# foArduinoMega.net
KiCad netlist of a schematic drawn in EAGLE
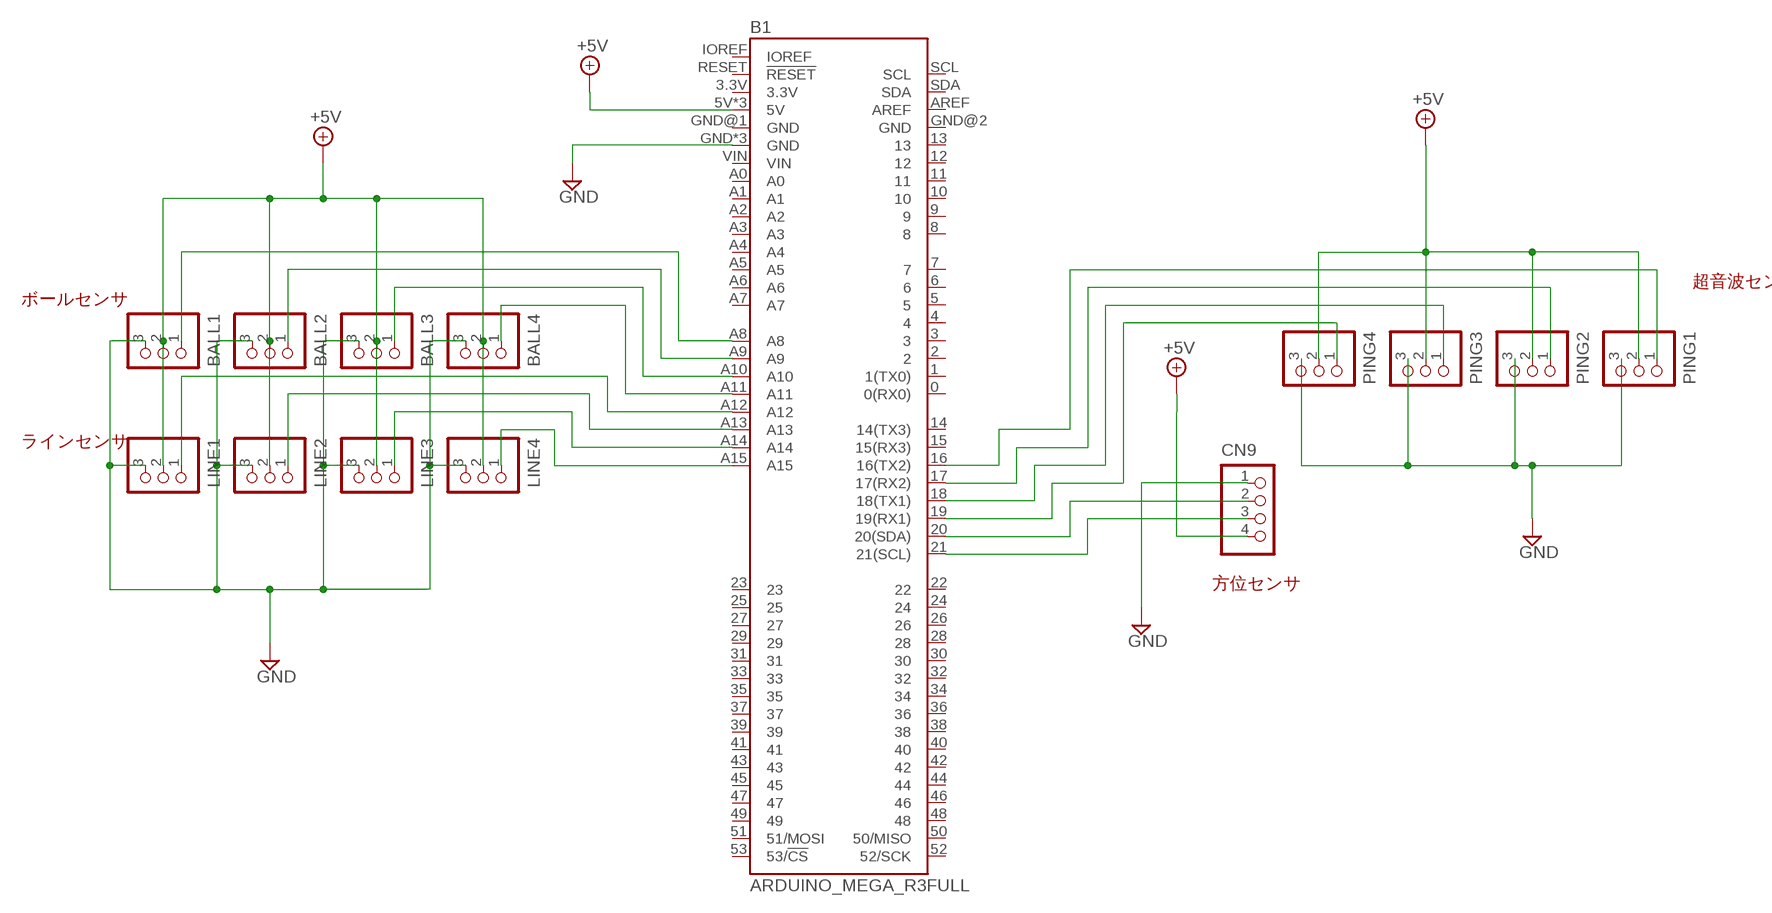
[diagram p0: schematic, sheet 1]

(export (version "E")
  (design (tool "Eeschema 10.0.6"))
  (components
    (comp (ref "B1")
      (value "ARDUINO_MEGA_R3FULL")
      (footprint "eagle-import:ARDUINO_MEGA_NO_SILK")
      (libsource (lib "eagle-import") (part "ARDUINO_MEGA_R3FULL"))
    )
    (comp (ref "BALL1")
      (value "B3B-XH-A")
      (footprint "eagle-import:B3B-XH-A")
      (libsource (lib "eagle-import") (part "B3B-XH-A"))
    )
    (comp (ref "BALL2")
      (value "B3B-XH-A")
      (footprint "eagle-import:B3B-XH-A")
      (libsource (lib "eagle-import") (part "B3B-XH-A"))
    )
    (comp (ref "BALL3")
      (value "B3B-XH-A")
      (footprint "eagle-import:B3B-XH-A")
      (libsource (lib "eagle-import") (part "B3B-XH-A"))
    )
    (comp (ref "BALL4")
      (value "B3B-XH-A")
      (footprint "eagle-import:B3B-XH-A")
      (libsource (lib "eagle-import") (part "B3B-XH-A"))
    )
    (comp (ref "CN9")
      (value "B4B-XH-A")
      (footprint "eagle-import:B4B-XH-A")
      (libsource (lib "eagle-import") (part "B4B-XH-A"))
    )
    (comp (ref "LINE1")
      (value "B3B-XH-A")
      (footprint "eagle-import:B3B-XH-A")
      (libsource (lib "eagle-import") (part "B3B-XH-A"))
    )
    (comp (ref "LINE2")
      (value "B3B-XH-A")
      (footprint "eagle-import:B3B-XH-A")
      (libsource (lib "eagle-import") (part "B3B-XH-A"))
    )
    (comp (ref "LINE3")
      (value "B3B-XH-A")
      (footprint "eagle-import:B3B-XH-A")
      (libsource (lib "eagle-import") (part "B3B-XH-A"))
    )
    (comp (ref "LINE4")
      (value "B3B-XH-A")
      (footprint "eagle-import:B3B-XH-A")
      (libsource (lib "eagle-import") (part "B3B-XH-A"))
    )
    (comp (ref "PING1")
      (value "B3B-XH-A")
      (footprint "eagle-import:B3B-XH-A")
      (libsource (lib "eagle-import") (part "B3B-XH-A"))
    )
    (comp (ref "PING2")
      (value "B3B-XH-A")
      (footprint "eagle-import:B3B-XH-A")
      (libsource (lib "eagle-import") (part "B3B-XH-A"))
    )
    (comp (ref "PING3")
      (value "B3B-XH-A")
      (footprint "eagle-import:B3B-XH-A")
      (libsource (lib "eagle-import") (part "B3B-XH-A"))
    )
    (comp (ref "PING4")
      (value "B3B-XH-A")
      (footprint "eagle-import:B3B-XH-A")
      (libsource (lib "eagle-import") (part "B3B-XH-A"))
    )
  )
  (nets
    (net (code "1") (name "+5V") (class "Default")
      (node (ref "B1") (pin "5V") (pinfunction "5V_5V") (pintype "bidirectional"))
      (node (ref "B1") (pin "5V@1") (pinfunction "5V_5V@1") (pintype "bidirectional"))
      (node (ref "B1") (pin "5V@2") (pinfunction "5V_5V@2") (pintype "bidirectional"))
      (node (ref "BALL1") (pin "2") (pinfunction "2_2") (pintype "passive"))
      (node (ref "BALL2") (pin "2") (pinfunction "2_2") (pintype "passive"))
      (node (ref "BALL3") (pin "2") (pinfunction "2_2") (pintype "passive"))
      (node (ref "BALL4") (pin "2") (pinfunction "2_2") (pintype "passive"))
      (node (ref "CN9") (pin "4") (pinfunction "4_4") (pintype "passive"))
      (node (ref "LINE1") (pin "2") (pinfunction "2_2") (pintype "passive"))
      (node (ref "LINE2") (pin "2") (pinfunction "2_2") (pintype "passive"))
      (node (ref "LINE3") (pin "2") (pinfunction "2_2") (pintype "passive"))
      (node (ref "LINE4") (pin "2") (pinfunction "2_2") (pintype "passive"))
      (node (ref "PING1") (pin "2") (pinfunction "2_2") (pintype "passive"))
      (node (ref "PING2") (pin "2") (pinfunction "2_2") (pintype "passive"))
      (node (ref "PING3") (pin "2") (pinfunction "2_2") (pintype "passive"))
      (node (ref "PING4") (pin "2") (pinfunction "2_2") (pintype "passive"))
    )
    (net (code "2") (name "GND") (class "Default")
      (node (ref "B1") (pin "GND") (pinfunction "GND_GND") (pintype "bidirectional"))
      (node (ref "B1") (pin "GND@3") (pinfunction "GND_GND@3") (pintype "bidirectional"))
      (node (ref "B1") (pin "GND@4") (pinfunction "GND_GND@4") (pintype "bidirectional"))
      (node (ref "BALL1") (pin "3") (pinfunction "3_3") (pintype "passive"))
      (node (ref "BALL2") (pin "3") (pinfunction "3_3") (pintype "passive"))
      (node (ref "BALL3") (pin "3") (pinfunction "3_3") (pintype "passive"))
      (node (ref "BALL4") (pin "3") (pinfunction "3_3") (pintype "passive"))
      (node (ref "CN9") (pin "1") (pinfunction "1_1") (pintype "passive"))
      (node (ref "LINE1") (pin "3") (pinfunction "3_3") (pintype "passive"))
      (node (ref "LINE2") (pin "3") (pinfunction "3_3") (pintype "passive"))
      (node (ref "LINE3") (pin "3") (pinfunction "3_3") (pintype "passive"))
      (node (ref "LINE4") (pin "3") (pinfunction "3_3") (pintype "passive"))
      (node (ref "PING1") (pin "3") (pinfunction "3_3") (pintype "passive"))
      (node (ref "PING2") (pin "3") (pinfunction "3_3") (pintype "passive"))
      (node (ref "PING3") (pin "3") (pinfunction "3_3") (pintype "passive"))
      (node (ref "PING4") (pin "3") (pinfunction "3_3") (pintype "passive"))
    )
    (net (code "3") (name "Net-(B1-16(TX2))") (class "Default")
      (node (ref "B1") (pin "16") (pinfunction "16(TX2)_16") (pintype "bidirectional"))
      (node (ref "PING1") (pin "1") (pinfunction "1_1") (pintype "passive"))
    )
    (net (code "4") (name "Net-(B1-17(RX2))") (class "Default")
      (node (ref "B1") (pin "17") (pinfunction "17(RX2)_17") (pintype "bidirectional"))
      (node (ref "PING2") (pin "1") (pinfunction "1_1") (pintype "passive"))
    )
    (net (code "5") (name "Net-(B1-18(TX1))") (class "Default")
      (node (ref "B1") (pin "18") (pinfunction "18(TX1)_18") (pintype "bidirectional"))
      (node (ref "PING3") (pin "1") (pinfunction "1_1") (pintype "passive"))
    )
    (net (code "6") (name "Net-(B1-19(RX1))") (class "Default")
      (node (ref "B1") (pin "19") (pinfunction "19(RX1)_19") (pintype "bidirectional"))
      (node (ref "PING4") (pin "1") (pinfunction "1_1") (pintype "passive"))
    )
    (net (code "7") (name "Net-(B1-20(SDA))") (class "Default")
      (node (ref "B1") (pin "20") (pinfunction "20(SDA)_20") (pintype "bidirectional"))
      (node (ref "CN9") (pin "2") (pinfunction "2_2") (pintype "passive"))
    )
    (net (code "8") (name "Net-(B1-21(SCL))") (class "Default")
      (node (ref "B1") (pin "21") (pinfunction "21(SCL)_21") (pintype "bidirectional"))
      (node (ref "CN9") (pin "3") (pinfunction "3_3") (pintype "passive"))
    )
    (net (code "9") (name "Net-(B1-PadA8)") (class "Default")
      (node (ref "B1") (pin "A8") (pinfunction "A8_A8") (pintype "bidirectional"))
      (node (ref "BALL1") (pin "1") (pinfunction "1_1") (pintype "passive"))
    )
    (net (code "10") (name "Net-(B1-PadA9)") (class "Default")
      (node (ref "B1") (pin "A9") (pinfunction "A9_A9") (pintype "bidirectional"))
      (node (ref "BALL2") (pin "1") (pinfunction "1_1") (pintype "passive"))
    )
    (net (code "11") (name "Net-(B1-PadA10)") (class "Default")
      (node (ref "B1") (pin "A10") (pinfunction "A10_A10") (pintype "bidirectional"))
      (node (ref "BALL3") (pin "1") (pinfunction "1_1") (pintype "passive"))
    )
    (net (code "12") (name "Net-(B1-PadA11)") (class "Default")
      (node (ref "B1") (pin "A11") (pinfunction "A11_A11") (pintype "bidirectional"))
      (node (ref "BALL4") (pin "1") (pinfunction "1_1") (pintype "passive"))
    )
    (net (code "13") (name "Net-(B1-PadA12)") (class "Default")
      (node (ref "B1") (pin "A12") (pinfunction "A12_A12") (pintype "bidirectional"))
      (node (ref "LINE1") (pin "1") (pinfunction "1_1") (pintype "passive"))
    )
    (net (code "14") (name "Net-(B1-PadA13)") (class "Default")
      (node (ref "B1") (pin "A13") (pinfunction "A13_A13") (pintype "bidirectional"))
      (node (ref "LINE2") (pin "1") (pinfunction "1_1") (pintype "passive"))
    )
    (net (code "15") (name "Net-(B1-PadA14)") (class "Default")
      (node (ref "B1") (pin "A14") (pinfunction "A14_A14") (pintype "bidirectional"))
      (node (ref "LINE3") (pin "1") (pinfunction "1_1") (pintype "passive"))
    )
    (net (code "16") (name "Net-(B1-PadA15)") (class "Default")
      (node (ref "B1") (pin "A15") (pinfunction "A15_A15") (pintype "bidirectional"))
      (node (ref "LINE4") (pin "1") (pinfunction "1_1") (pintype "passive"))
    )
    (net (code "17") (name "unconnected-(B1-0(RX0)-Pad0)") (class "Default")
      (node (ref "B1") (pin "0") (pinfunction "0(RX0)_0") (pintype "bidirectional"))
    )
    (net (code "18") (name "unconnected-(B1-1(TX0)-Pad1)") (class "Default")
      (node (ref "B1") (pin "1") (pinfunction "1(TX0)_1") (pintype "bidirectional"))
    )
    (net (code "19") (name "unconnected-(B1-14(TX3)-Pad14)") (class "Default")
      (node (ref "B1") (pin "14") (pinfunction "14(TX3)_14") (pintype "bidirectional"))
    )
    (net (code "20") (name "unconnected-(B1-15(RX3)-Pad15)") (class "Default")
      (node (ref "B1") (pin "15") (pinfunction "15(RX3)_15") (pintype "bidirectional"))
    )
    (net (code "21") (name "unconnected-(B1-50{slash}MISO-Pad50)") (class "Default")
      (node (ref "B1") (pin "50") (pinfunction "50/MISO_50") (pintype "bidirectional"))
    )
    (net (code "22") (name "unconnected-(B1-51{slash}MOSI-Pad51)") (class "Default")
      (node (ref "B1") (pin "51") (pinfunction "51/MOSI_51") (pintype "bidirectional"))
    )
    (net (code "23") (name "unconnected-(B1-52{slash}SCK-Pad52)") (class "Default")
      (node (ref "B1") (pin "52") (pinfunction "52/SCK_52") (pintype "bidirectional"))
    )
    (net (code "24") (name "unconnected-(B1-53{slash}~{CS}-Pad53)") (class "Default")
      (node (ref "B1") (pin "53") (pinfunction "53/~{CS}_53") (pintype "bidirectional"))
    )
    (net (code "25") (name "unconnected-(B1-GND-PadGND@1)") (class "Default")
      (node (ref "B1") (pin "GND@1") (pinfunction "GND_GND@1") (pintype "bidirectional"))
    )
    (net (code "26") (name "unconnected-(B1-GND-PadGND@2)") (class "Default")
      (node (ref "B1") (pin "GND@2") (pinfunction "GND_GND@2") (pintype "bidirectional"))
    )
    (net (code "27") (name "unconnected-(B1-Pad2)") (class "Default")
      (node (ref "B1") (pin "2") (pinfunction "2_2") (pintype "bidirectional"))
    )
    (net (code "28") (name "unconnected-(B1-Pad3)") (class "Default")
      (node (ref "B1") (pin "3") (pinfunction "3_3") (pintype "bidirectional"))
    )
    (net (code "29") (name "unconnected-(B1-Pad3.3V)") (class "Default")
      (node (ref "B1") (pin "3.3V") (pinfunction "3.3V_3.3V") (pintype "bidirectional"))
    )
    (net (code "30") (name "unconnected-(B1-Pad4)") (class "Default")
      (node (ref "B1") (pin "4") (pinfunction "4_4") (pintype "bidirectional"))
    )
    (net (code "31") (name "unconnected-(B1-Pad5)") (class "Default")
      (node (ref "B1") (pin "5") (pinfunction "5_5") (pintype "bidirectional"))
    )
    (net (code "32") (name "unconnected-(B1-Pad6)") (class "Default")
      (node (ref "B1") (pin "6") (pinfunction "6_6") (pintype "bidirectional"))
    )
    (net (code "33") (name "unconnected-(B1-Pad7)") (class "Default")
      (node (ref "B1") (pin "7") (pinfunction "7_7") (pintype "bidirectional"))
    )
    (net (code "34") (name "unconnected-(B1-Pad8)") (class "Default")
      (node (ref "B1") (pin "8") (pinfunction "8_8") (pintype "bidirectional"))
    )
    (net (code "35") (name "unconnected-(B1-Pad9)") (class "Default")
      (node (ref "B1") (pin "9") (pinfunction "9_9") (pintype "bidirectional"))
    )
    (net (code "36") (name "unconnected-(B1-Pad10)") (class "Default")
      (node (ref "B1") (pin "10") (pinfunction "10_10") (pintype "bidirectional"))
    )
    (net (code "37") (name "unconnected-(B1-Pad11)") (class "Default")
      (node (ref "B1") (pin "11") (pinfunction "11_11") (pintype "bidirectional"))
    )
    (net (code "38") (name "unconnected-(B1-Pad12)") (class "Default")
      (node (ref "B1") (pin "12") (pinfunction "12_12") (pintype "bidirectional"))
    )
    (net (code "39") (name "unconnected-(B1-Pad13)") (class "Default")
      (node (ref "B1") (pin "13") (pinfunction "13_13") (pintype "bidirectional"))
    )
    (net (code "40") (name "unconnected-(B1-Pad22)") (class "Default")
      (node (ref "B1") (pin "22") (pinfunction "22_22") (pintype "bidirectional"))
    )
    (net (code "41") (name "unconnected-(B1-Pad23)") (class "Default")
      (node (ref "B1") (pin "23") (pinfunction "23_23") (pintype "bidirectional"))
    )
    (net (code "42") (name "unconnected-(B1-Pad24)") (class "Default")
      (node (ref "B1") (pin "24") (pinfunction "24_24") (pintype "bidirectional"))
    )
    (net (code "43") (name "unconnected-(B1-Pad25)") (class "Default")
      (node (ref "B1") (pin "25") (pinfunction "25_25") (pintype "bidirectional"))
    )
    (net (code "44") (name "unconnected-(B1-Pad26)") (class "Default")
      (node (ref "B1") (pin "26") (pinfunction "26_26") (pintype "bidirectional"))
    )
    (net (code "45") (name "unconnected-(B1-Pad27)") (class "Default")
      (node (ref "B1") (pin "27") (pinfunction "27_27") (pintype "bidirectional"))
    )
    (net (code "46") (name "unconnected-(B1-Pad28)") (class "Default")
      (node (ref "B1") (pin "28") (pinfunction "28_28") (pintype "bidirectional"))
    )
    (net (code "47") (name "unconnected-(B1-Pad29)") (class "Default")
      (node (ref "B1") (pin "29") (pinfunction "29_29") (pintype "bidirectional"))
    )
    (net (code "48") (name "unconnected-(B1-Pad30)") (class "Default")
      (node (ref "B1") (pin "30") (pinfunction "30_30") (pintype "bidirectional"))
    )
    (net (code "49") (name "unconnected-(B1-Pad31)") (class "Default")
      (node (ref "B1") (pin "31") (pinfunction "31_31") (pintype "bidirectional"))
    )
    (net (code "50") (name "unconnected-(B1-Pad32)") (class "Default")
      (node (ref "B1") (pin "32") (pinfunction "32_32") (pintype "bidirectional"))
    )
    (net (code "51") (name "unconnected-(B1-Pad33)") (class "Default")
      (node (ref "B1") (pin "33") (pinfunction "33_33") (pintype "bidirectional"))
    )
    (net (code "52") (name "unconnected-(B1-Pad34)") (class "Default")
      (node (ref "B1") (pin "34") (pinfunction "34_34") (pintype "bidirectional"))
    )
    (net (code "53") (name "unconnected-(B1-Pad35)") (class "Default")
      (node (ref "B1") (pin "35") (pinfunction "35_35") (pintype "bidirectional"))
    )
    (net (code "54") (name "unconnected-(B1-Pad36)") (class "Default")
      (node (ref "B1") (pin "36") (pinfunction "36_36") (pintype "bidirectional"))
    )
    (net (code "55") (name "unconnected-(B1-Pad37)") (class "Default")
      (node (ref "B1") (pin "37") (pinfunction "37_37") (pintype "bidirectional"))
    )
    (net (code "56") (name "unconnected-(B1-Pad38)") (class "Default")
      (node (ref "B1") (pin "38") (pinfunction "38_38") (pintype "bidirectional"))
    )
    (net (code "57") (name "unconnected-(B1-Pad39)") (class "Default")
      (node (ref "B1") (pin "39") (pinfunction "39_39") (pintype "bidirectional"))
    )
    (net (code "58") (name "unconnected-(B1-Pad40)") (class "Default")
      (node (ref "B1") (pin "40") (pinfunction "40_40") (pintype "bidirectional"))
    )
    (net (code "59") (name "unconnected-(B1-Pad41)") (class "Default")
      (node (ref "B1") (pin "41") (pinfunction "41_41") (pintype "bidirectional"))
    )
    (net (code "60") (name "unconnected-(B1-Pad42)") (class "Default")
      (node (ref "B1") (pin "42") (pinfunction "42_42") (pintype "bidirectional"))
    )
    (net (code "61") (name "unconnected-(B1-Pad43)") (class "Default")
      (node (ref "B1") (pin "43") (pinfunction "43_43") (pintype "bidirectional"))
    )
    (net (code "62") (name "unconnected-(B1-Pad44)") (class "Default")
      (node (ref "B1") (pin "44") (pinfunction "44_44") (pintype "bidirectional"))
    )
    (net (code "63") (name "unconnected-(B1-Pad45)") (class "Default")
      (node (ref "B1") (pin "45") (pinfunction "45_45") (pintype "bidirectional"))
    )
    (net (code "64") (name "unconnected-(B1-Pad46)") (class "Default")
      (node (ref "B1") (pin "46") (pinfunction "46_46") (pintype "bidirectional"))
    )
    (net (code "65") (name "unconnected-(B1-Pad47)") (class "Default")
      (node (ref "B1") (pin "47") (pinfunction "47_47") (pintype "bidirectional"))
    )
    (net (code "66") (name "unconnected-(B1-Pad48)") (class "Default")
      (node (ref "B1") (pin "48") (pinfunction "48_48") (pintype "bidirectional"))
    )
    (net (code "67") (name "unconnected-(B1-Pad49)") (class "Default")
      (node (ref "B1") (pin "49") (pinfunction "49_49") (pintype "bidirectional"))
    )
    (net (code "68") (name "unconnected-(B1-PadA0)") (class "Default")
      (node (ref "B1") (pin "A0") (pinfunction "A0_A0") (pintype "bidirectional"))
    )
    (net (code "69") (name "unconnected-(B1-PadA1)") (class "Default")
      (node (ref "B1") (pin "A1") (pinfunction "A1_A1") (pintype "bidirectional"))
    )
    (net (code "70") (name "unconnected-(B1-PadA2)") (class "Default")
      (node (ref "B1") (pin "A2") (pinfunction "A2_A2") (pintype "bidirectional"))
    )
    (net (code "71") (name "unconnected-(B1-PadA3)") (class "Default")
      (node (ref "B1") (pin "A3") (pinfunction "A3_A3") (pintype "bidirectional"))
    )
    (net (code "72") (name "unconnected-(B1-PadA4)") (class "Default")
      (node (ref "B1") (pin "A4") (pinfunction "A4_A4") (pintype "bidirectional"))
    )
    (net (code "73") (name "unconnected-(B1-PadA5)") (class "Default")
      (node (ref "B1") (pin "A5") (pinfunction "A5_A5") (pintype "bidirectional"))
    )
    (net (code "74") (name "unconnected-(B1-PadA6)") (class "Default")
      (node (ref "B1") (pin "A6") (pinfunction "A6_A6") (pintype "bidirectional"))
    )
    (net (code "75") (name "unconnected-(B1-PadA7)") (class "Default")
      (node (ref "B1") (pin "A7") (pinfunction "A7_A7") (pintype "bidirectional"))
    )
    (net (code "76") (name "unconnected-(B1-PadAREF)") (class "Default")
      (node (ref "B1") (pin "AREF") (pinfunction "AREF_AREF") (pintype "bidirectional"))
    )
    (net (code "77") (name "unconnected-(B1-PadIOREF)") (class "Default")
      (node (ref "B1") (pin "IOREF") (pinfunction "IOREF_IOREF") (pintype "bidirectional"))
    )
    (net (code "78") (name "unconnected-(B1-PadSCL)") (class "Default")
      (node (ref "B1") (pin "SCL") (pinfunction "SCL_SCL") (pintype "bidirectional"))
    )
    (net (code "79") (name "unconnected-(B1-PadSDA)") (class "Default")
      (node (ref "B1") (pin "SDA") (pinfunction "SDA_SDA") (pintype "bidirectional"))
    )
    (net (code "80") (name "unconnected-(B1-PadVIN)") (class "Default")
      (node (ref "B1") (pin "VIN") (pinfunction "VIN_VIN") (pintype "bidirectional"))
    )
    (net (code "81") (name "unconnected-(B1-~{RESET}-PadRESET)") (class "Default")
      (node (ref "B1") (pin "RESET") (pinfunction "~{RESET}_RESET") (pintype "bidirectional"))
    )
  )
)
